# TOP_pcb_redonda_definitiva.net
KiCad netlist of a schematic drawn in EAGLE
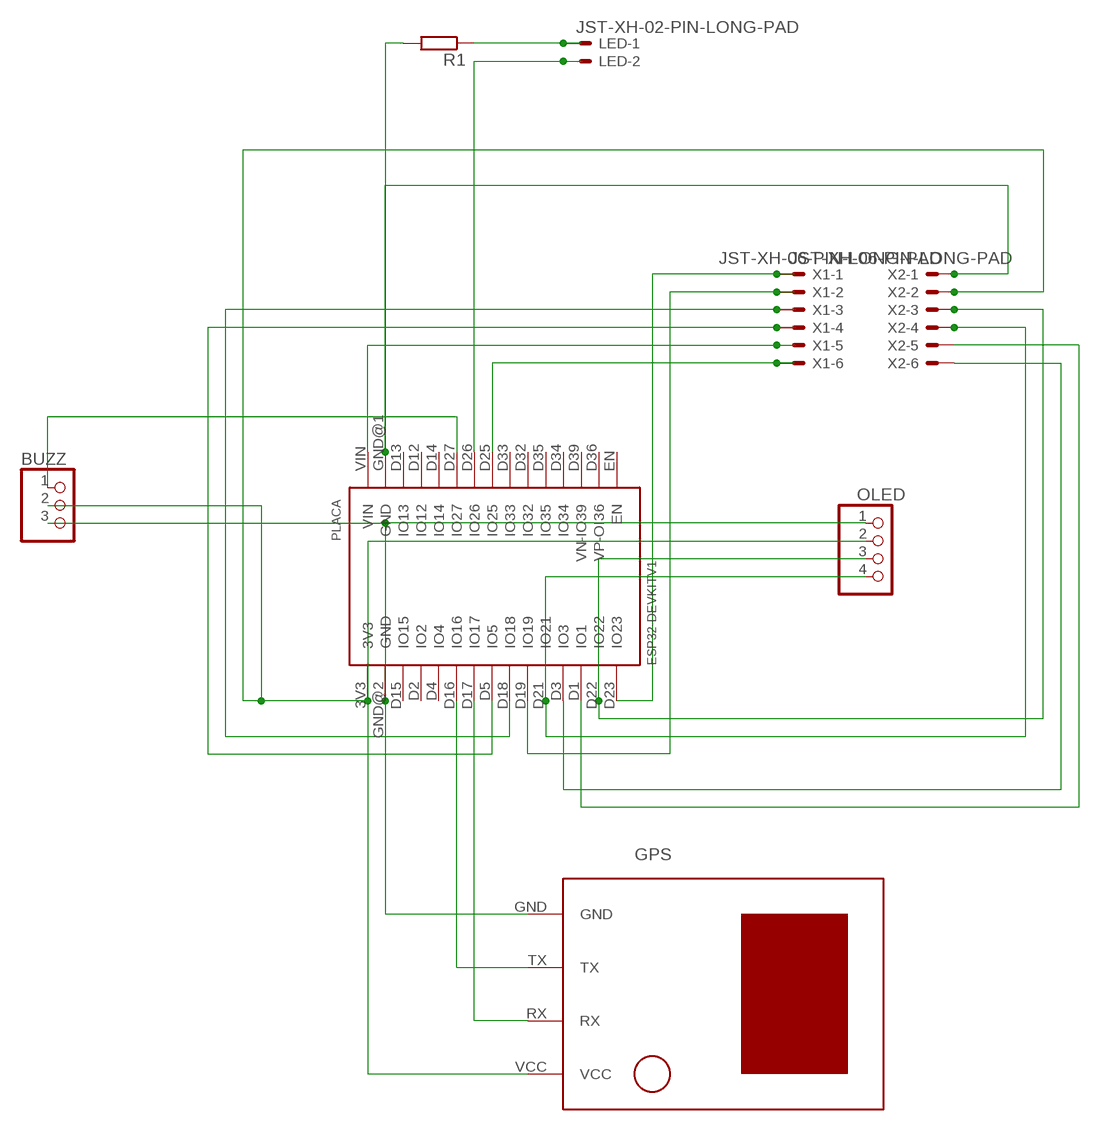
[diagram p0: schematic, sheet 1]

(export (version "E")
  (design (tool "Eeschema 10.0.6"))
  (components
    (comp (ref "BUZZ")
      (value "PINHD-1X3")
      (footprint "eagle-import:1X03")
      (libsource (lib "eagle-import") (part "PINHD-1X3"))
    )
    (comp (ref "GPS")
      (value "U-BLOX-NEO6V2")
      (footprint "eagle-import:U-BLOX-NEO6V2")
      (libsource (lib "eagle-import") (part "U-BLOX-NEO6V2"))
    )
    (comp (ref "LED")
      (value "JST-XH-02-PIN-LONG-PAD")
      (footprint "eagle-import:JST-XH-02-PACKAGE-LONG-PAD")
      (libsource (lib "eagle-import") (part "JST-XH-02-PIN-LONG-PAD"))
    )
    (comp (ref "OLED")
      (value "PINHD-1X4")
      (footprint "eagle-import:1X04")
      (libsource (lib "eagle-import") (part "PINHD-1X4"))
    )
    (comp (ref "PLACA")
      (value "ESP32DEVKITV1")
      (footprint "eagle-import:ESP32-DEVKITV1")
      (libsource (lib "eagle-import") (part "ESP32DEVKITV1"))
    )
    (comp (ref "R1")
      (value "R-EU_0207/10")
      (footprint "eagle-import:0207_10")
      (libsource (lib "eagle-import") (part "R-EU_0207/10"))
    )
    (comp (ref "X1")
      (value "JST-XH-06-PIN-LONG-PAD")
      (footprint "eagle-import:JST-XH-06-PACKAGE-LONG-PAD")
      (libsource (lib "eagle-import") (part "JST-XH-06-PIN-LONG-PAD"))
    )
    (comp (ref "X2")
      (value "JST-XH-06-PIN-LONG-PAD")
      (footprint "eagle-import:JST-XH-06-PACKAGE-LONG-PAD")
      (libsource (lib "eagle-import") (part "JST-XH-06-PIN-LONG-PAD"))
    )
  )
  (nets
    (net (code "1") (name "/GPS") (class "Default")
      (node (ref "BUZZ") (pin "3") (pinfunction "3_3") (pintype "passive"))
      (node (ref "GPS") (pin "GND") (pinfunction "GND_GND") (pintype "bidirectional"))
      (node (ref "OLED") (pin "1") (pinfunction "1_1") (pintype "passive"))
      (node (ref "PLACA") (pin "GND@2") (pinfunction "GND_GND@2") (pintype "bidirectional"))
    )
    (net (code "2") (name "Net-(LEDA-S)") (class "Default")
      (node (ref "LED") (pin "1") (pinfunction "S_1") (pintype "passive"))
      (node (ref "R1") (pin "1") (pinfunction "1_1") (pintype "passive"))
    )
    (net (code "3") (name "Net-(LEDB-S)") (class "Default")
      (node (ref "LED") (pin "2") (pinfunction "S_2") (pintype "passive"))
      (node (ref "PLACA") (pin "D26") (pinfunction "IO26_D26") (pintype "bidirectional"))
    )
    (net (code "4") (name "Net-(PLACA-IO1)") (class "Default")
      (node (ref "PLACA") (pin "D1") (pinfunction "IO1_D1") (pintype "bidirectional"))
      (node (ref "X2") (pin "5") (pinfunction "S_5") (pintype "passive"))
    )
    (net (code "5") (name "Net-(PLACA-IO3)") (class "Default")
      (node (ref "PLACA") (pin "D3") (pinfunction "IO3_D3") (pintype "bidirectional"))
      (node (ref "X2") (pin "6") (pinfunction "S_6") (pintype "passive"))
    )
    (net (code "6") (name "Net-(PLACA-IO5)") (class "Default")
      (node (ref "PLACA") (pin "D5") (pinfunction "IO5_D5") (pintype "bidirectional"))
      (node (ref "X1") (pin "4") (pinfunction "S_4") (pintype "passive"))
    )
    (net (code "7") (name "Net-(PLACA-IO16)") (class "Default")
      (node (ref "GPS") (pin "TX") (pinfunction "TX_TX") (pintype "bidirectional"))
      (node (ref "PLACA") (pin "D16") (pinfunction "IO16_D16") (pintype "bidirectional"))
    )
    (net (code "8") (name "Net-(PLACA-IO17)") (class "Default")
      (node (ref "GPS") (pin "RX") (pinfunction "RX_RX") (pintype "bidirectional"))
      (node (ref "PLACA") (pin "D17") (pinfunction "IO17_D17") (pintype "bidirectional"))
    )
    (net (code "9") (name "Net-(PLACA-IO18)") (class "Default")
      (node (ref "PLACA") (pin "D18") (pinfunction "IO18_D18") (pintype "bidirectional"))
      (node (ref "X1") (pin "3") (pinfunction "S_3") (pintype "passive"))
    )
    (net (code "10") (name "Net-(PLACA-IO19)") (class "Default")
      (node (ref "PLACA") (pin "D19") (pinfunction "IO19_D19") (pintype "bidirectional"))
      (node (ref "X1") (pin "2") (pinfunction "S_2") (pintype "passive"))
    )
    (net (code "11") (name "Net-(PLACA-IO21)") (class "Default")
      (node (ref "OLED") (pin "4") (pinfunction "4_4") (pintype "passive"))
      (node (ref "PLACA") (pin "D21") (pinfunction "IO21_D21") (pintype "bidirectional"))
      (node (ref "X2") (pin "4") (pinfunction "S_4") (pintype "passive"))
    )
    (net (code "12") (name "Net-(PLACA-IO22)") (class "Default")
      (node (ref "OLED") (pin "3") (pinfunction "3_3") (pintype "passive"))
      (node (ref "PLACA") (pin "D22") (pinfunction "IO22_D22") (pintype "bidirectional"))
      (node (ref "X2") (pin "3") (pinfunction "S_3") (pintype "passive"))
    )
    (net (code "13") (name "Net-(PLACA-IO23)") (class "Default")
      (node (ref "PLACA") (pin "D23") (pinfunction "IO23_D23") (pintype "bidirectional"))
      (node (ref "X1") (pin "1") (pinfunction "S_1") (pintype "passive"))
    )
    (net (code "14") (name "Net-(PLACA-IO25)") (class "Default")
      (node (ref "PLACA") (pin "D25") (pinfunction "IO25_D25") (pintype "bidirectional"))
      (node (ref "X1") (pin "6") (pinfunction "S_6") (pintype "passive"))
    )
    (net (code "15") (name "Net-(PLACA-IO27)") (class "Default")
      (node (ref "BUZZ") (pin "1") (pinfunction "1_1") (pintype "passive"))
      (node (ref "PLACA") (pin "D27") (pinfunction "IO27_D27") (pintype "bidirectional"))
    )
    (net (code "16") (name "Net-(X1E-S)") (class "Default")
      (node (ref "PLACA") (pin "VIN") (pinfunction "VIN_VIN") (pintype "bidirectional"))
      (node (ref "X1") (pin "5") (pinfunction "S_5") (pintype "passive"))
    )
    (net (code "17") (name "Net-(X2A-S)") (class "Default")
      (node (ref "PLACA") (pin "GND@1") (pinfunction "GND_GND@1") (pintype "bidirectional"))
      (node (ref "R1") (pin "2") (pinfunction "2_2") (pintype "passive"))
      (node (ref "X2") (pin "1") (pinfunction "S_1") (pintype "passive"))
    )
    (net (code "18") (name "Net-(X2B-S)") (class "Default")
      (node (ref "BUZZ") (pin "2") (pinfunction "2_2") (pintype "passive"))
      (node (ref "GPS") (pin "VCC") (pinfunction "VCC_VCC") (pintype "bidirectional"))
      (node (ref "OLED") (pin "2") (pinfunction "2_2") (pintype "passive"))
      (node (ref "PLACA") (pin "3V3") (pinfunction "3V3_3V3") (pintype "bidirectional"))
      (node (ref "X2") (pin "2") (pinfunction "S_2") (pintype "passive"))
    )
    (net (code "19") (name "unconnected-(PLACA-IO2-PadD2)") (class "Default")
      (node (ref "PLACA") (pin "D2") (pinfunction "IO2_D2") (pintype "bidirectional"))
    )
    (net (code "20") (name "unconnected-(PLACA-IO4-PadD4)") (class "Default")
      (node (ref "PLACA") (pin "D4") (pinfunction "IO4_D4") (pintype "bidirectional"))
    )
    (net (code "21") (name "unconnected-(PLACA-IO12-PadD12)") (class "Default")
      (node (ref "PLACA") (pin "D12") (pinfunction "IO12_D12") (pintype "bidirectional"))
    )
    (net (code "22") (name "unconnected-(PLACA-IO13-PadD13)") (class "Default")
      (node (ref "PLACA") (pin "D13") (pinfunction "IO13_D13") (pintype "bidirectional"))
    )
    (net (code "23") (name "unconnected-(PLACA-IO14-PadD14)") (class "Default")
      (node (ref "PLACA") (pin "D14") (pinfunction "IO14_D14") (pintype "bidirectional"))
    )
    (net (code "24") (name "unconnected-(PLACA-IO15-PadD15)") (class "Default")
      (node (ref "PLACA") (pin "D15") (pinfunction "IO15_D15") (pintype "bidirectional"))
    )
    (net (code "25") (name "unconnected-(PLACA-IO32-PadD32)") (class "Default")
      (node (ref "PLACA") (pin "D32") (pinfunction "IO32_D32") (pintype "bidirectional"))
    )
    (net (code "26") (name "unconnected-(PLACA-IO33-PadD33)") (class "Default")
      (node (ref "PLACA") (pin "D33") (pinfunction "IO33_D33") (pintype "bidirectional"))
    )
    (net (code "27") (name "unconnected-(PLACA-IO34-PadD34)") (class "Default")
      (node (ref "PLACA") (pin "D34") (pinfunction "IO34_D34") (pintype "bidirectional"))
    )
    (net (code "28") (name "unconnected-(PLACA-IO35-PadD35)") (class "Default")
      (node (ref "PLACA") (pin "D35") (pinfunction "IO35_D35") (pintype "bidirectional"))
    )
    (net (code "29") (name "unconnected-(PLACA-PadEN)") (class "Default")
      (node (ref "PLACA") (pin "EN") (pinfunction "EN_EN") (pintype "bidirectional"))
    )
    (net (code "30") (name "unconnected-(PLACA-VN-IO39-PadD39)") (class "Default")
      (node (ref "PLACA") (pin "D39") (pinfunction "VN-IO39_D39") (pintype "bidirectional"))
    )
    (net (code "31") (name "unconnected-(PLACA-VP-OI36-PadD36)") (class "Default")
      (node (ref "PLACA") (pin "D36") (pinfunction "VP-OI36_D36") (pintype "bidirectional"))
    )
  )
)
